# ATmega1284P.net
KiCad netlist of a schematic drawn in EAGLE
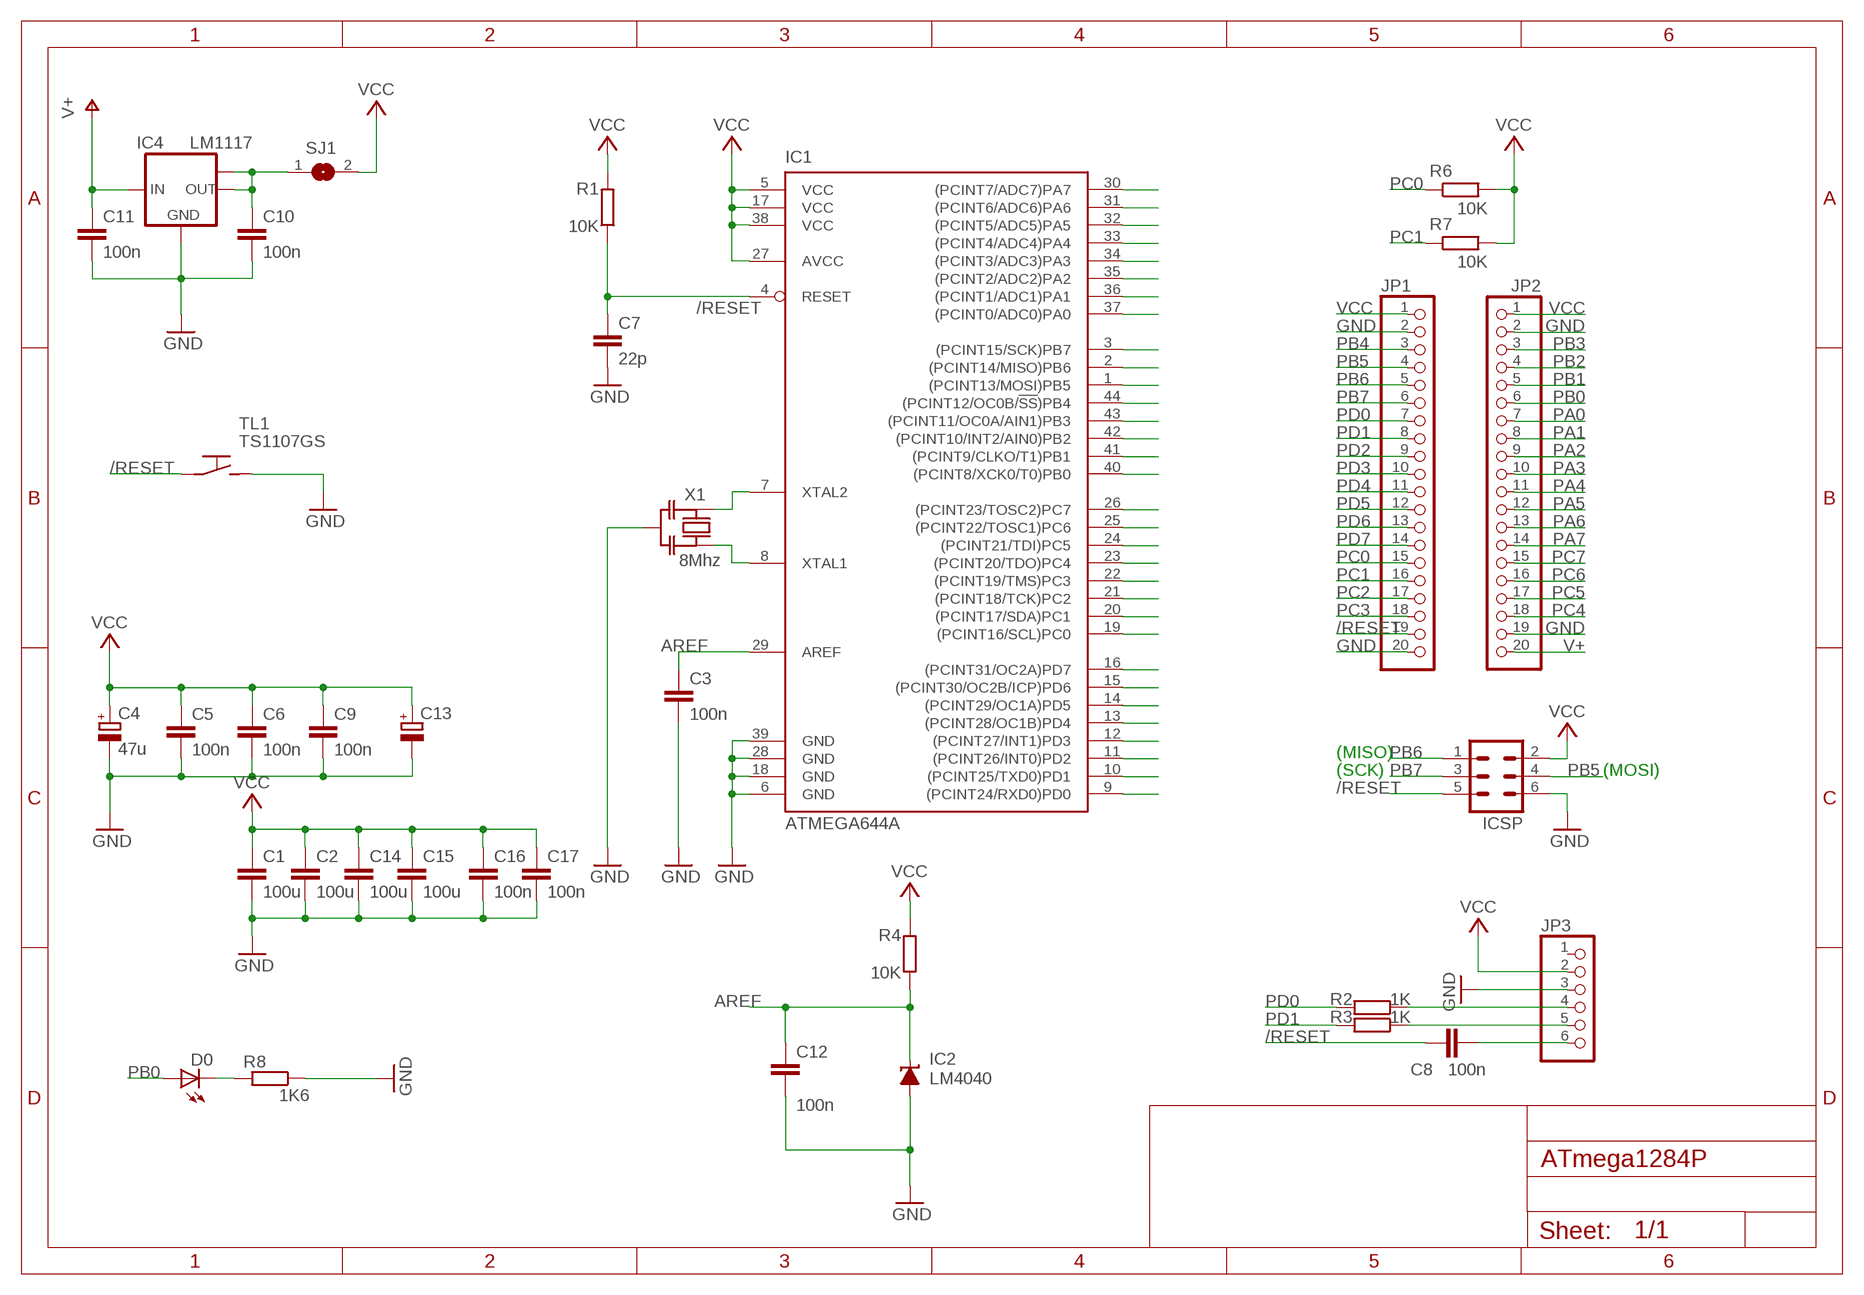
[diagram p0: schematic, sheet 1]

(export (version "E")
  (design (tool "Eeschema 10.0.6"))
  (components
    (comp (ref "C1")
      (value "100u")
      (footprint "eagle-import:C1206")
      (libsource (lib "eagle-import") (part "C-EUC1206"))
    )
    (comp (ref "C2")
      (value "100u")
      (footprint "eagle-import:C1206")
      (libsource (lib "eagle-import") (part "C-EUC1206"))
    )
    (comp (ref "C3")
      (value "100n")
      (footprint "eagle-import:C0805")
      (libsource (lib "eagle-import") (part "C-EUC0805"))
    )
    (comp (ref "C4")
      (value "47u")
      (footprint "eagle-import:SMC_A")
      (libsource (lib "eagle-import") (part "CPOL-EUSMCA"))
    )
    (comp (ref "C5")
      (value "100n")
      (footprint "eagle-import:C0805")
      (libsource (lib "eagle-import") (part "C-EUC0805"))
    )
    (comp (ref "C6")
      (value "100n")
      (footprint "eagle-import:C0805")
      (libsource (lib "eagle-import") (part "C-EUC0805"))
    )
    (comp (ref "C7")
      (value "22p")
      (footprint "eagle-import:C0805")
      (libsource (lib "eagle-import") (part "C-EUC0805"))
    )
    (comp (ref "C8")
      (value "100n")
      (footprint "eagle-import:C0805")
      (libsource (lib "eagle-import") (part "C-EUC0805"))
    )
    (comp (ref "C9")
      (value "100n")
      (footprint "eagle-import:C0805")
      (libsource (lib "eagle-import") (part "C-EUC0805"))
    )
    (comp (ref "C10")
      (value "100n")
      (footprint "eagle-import:C0805")
      (libsource (lib "eagle-import") (part "C-EUC0805"))
    )
    (comp (ref "C11")
      (value "100n")
      (footprint "eagle-import:C0805")
      (libsource (lib "eagle-import") (part "C-EUC0805"))
    )
    (comp (ref "C12")
      (value "100n")
      (footprint "eagle-import:C0805")
      (libsource (lib "eagle-import") (part "C-EUC0805"))
    )
    (comp (ref "C13")
      (value "CPOL-EUSMCC")
      (footprint "eagle-import:SMC_C")
      (libsource (lib "eagle-import") (part "CPOL-EUSMCC"))
    )
    (comp (ref "C14")
      (value "100u")
      (footprint "eagle-import:C1206")
      (libsource (lib "eagle-import") (part "C-EUC1206"))
    )
    (comp (ref "C15")
      (value "100u")
      (footprint "eagle-import:C1206")
      (libsource (lib "eagle-import") (part "C-EUC1206"))
    )
    (comp (ref "C16")
      (value "100n")
      (footprint "eagle-import:C0805")
      (libsource (lib "eagle-import") (part "C-EUC0805"))
    )
    (comp (ref "C17")
      (value "100n")
      (footprint "eagle-import:C0805")
      (libsource (lib "eagle-import") (part "C-EUC0805"))
    )
    (comp (ref "D0")
      (value "LEDCHIPLED_0805")
      (footprint "eagle-import:CHIPLED_0805")
      (libsource (lib "eagle-import") (part "LEDCHIPLED_0805"))
    )
    (comp (ref "IC1")
      (value "ATMEGA644A")
      (footprint "eagle-import:TQFP44")
      (fields (field (name "MPN") "ATMEGA644PV-10AU"))
      (libsource (lib "eagle-import") (part "ATMEGA644A"))
    )
    (comp (ref "IC2")
      (value "LM4040")
      (footprint "eagle-import:DBZ_R-PDSO-G3")
      (fields (field (name "MPN") "LM4041A12IDBZR"))
      (libsource (lib "eagle-import") (part "LM4041DBZA12"))
    )
    (comp (ref "IC4")
      (value "LM1117")
      (footprint "eagle-import:SOT223")
      (libsource (lib "eagle-import") (part "LM1117IMPX-3.3"))
    )
    (comp (ref "ICSP")
      (value "ML6")
      (footprint "eagle-import:ML6")
      (libsource (lib "eagle-import") (part "ML6"))
    )
    (comp (ref "JP1")
      (value "PINHD-1X20")
      (footprint "eagle-import:1X20")
      (libsource (lib "eagle-import") (part "PINHD-1X20"))
    )
    (comp (ref "JP2")
      (value "PINHD-1X20")
      (footprint "eagle-import:1X20")
      (libsource (lib "eagle-import") (part "PINHD-1X20"))
    )
    (comp (ref "JP3")
      (value "PINHD-1X6")
      (footprint "eagle-import:1X06")
      (libsource (lib "eagle-import") (part "PINHD-1X6"))
    )
    (comp (ref "R1")
      (value "10K")
      (footprint "eagle-import:M0805")
      (libsource (lib "eagle-import") (part "R-EU_M0805"))
    )
    (comp (ref "R2")
      (value "1K")
      (footprint "eagle-import:M0805")
      (libsource (lib "eagle-import") (part "R-EU_M0805"))
    )
    (comp (ref "R3")
      (value "1K")
      (footprint "eagle-import:M0805")
      (libsource (lib "eagle-import") (part "R-EU_M0805"))
    )
    (comp (ref "R4")
      (value "10K")
      (footprint "eagle-import:M0805")
      (libsource (lib "eagle-import") (part "R-EU_M0805"))
    )
    (comp (ref "R6")
      (value "10K")
      (footprint "eagle-import:M0805")
      (libsource (lib "eagle-import") (part "R-EU_M0805"))
    )
    (comp (ref "R7")
      (value "10K")
      (footprint "eagle-import:M0805")
      (libsource (lib "eagle-import") (part "R-EU_M0805"))
    )
    (comp (ref "R8")
      (value "1K6")
      (footprint "eagle-import:M0805")
      (libsource (lib "eagle-import") (part "R-EU_M0805"))
    )
    (comp (ref "SJ1") (value "SJ") (footprint "eagle-import:SJ") (libsource (lib "eagle-import") (part "SJ")))
    (comp (ref "TL1")
      (value "TS1107GS")
      (footprint "eagle-import:TS1107GS")
      (libsource (lib "eagle-import") (part "TS1107GS"))
    )
    (comp (ref "X1")
      (value "8Mhz")
      (footprint "eagle-import:CERALOCK_CSTCE_G")
      (libsource (lib "eagle-import") (part "CERMOSC-?CERALOCK-CSTCE_G"))
    )
  )
  (nets
    (net (code "1") (name "/AREF") (class "Default")
      (node (ref "C12") (pin "1") (pinfunction "1_1") (pintype "passive"))
      (node (ref "C3") (pin "2") (pinfunction "2_2") (pintype "passive"))
      (node (ref "IC1") (pin "29") (pinfunction "AREF_29") (pintype "passive"))
      (node (ref "IC2") (pin "1") (pinfunction "C_1") (pintype "passive"))
      (node (ref "R4") (pin "1") (pinfunction "1_1") (pintype "passive"))
    )
    (net (code "2") (name "/PA0") (class "Default")
      (node (ref "IC1") (pin "37") (pinfunction "(PCINT0/ADC0)PA0_37") (pintype "bidirectional"))
      (node (ref "JP2") (pin "7") (pinfunction "7_7") (pintype "passive"))
    )
    (net (code "3") (name "/PA1") (class "Default")
      (node (ref "IC1") (pin "36") (pinfunction "(PCINT1/ADC1)PA1_36") (pintype "bidirectional"))
      (node (ref "JP2") (pin "8") (pinfunction "8_8") (pintype "passive"))
    )
    (net (code "4") (name "/PA2") (class "Default")
      (node (ref "IC1") (pin "35") (pinfunction "(PCINT2/ADC2)PA2_35") (pintype "bidirectional"))
      (node (ref "JP2") (pin "9") (pinfunction "9_9") (pintype "passive"))
    )
    (net (code "5") (name "/PA3") (class "Default")
      (node (ref "IC1") (pin "34") (pinfunction "(PCINT3/ADC3)PA3_34") (pintype "bidirectional"))
      (node (ref "JP2") (pin "10") (pinfunction "10_10") (pintype "passive"))
    )
    (net (code "6") (name "/PA4") (class "Default")
      (node (ref "IC1") (pin "33") (pinfunction "(PCINT4/ADC4)PA4_33") (pintype "bidirectional"))
      (node (ref "JP2") (pin "11") (pinfunction "11_11") (pintype "passive"))
    )
    (net (code "7") (name "/PA5") (class "Default")
      (node (ref "IC1") (pin "32") (pinfunction "(PCINT5/ADC5)PA5_32") (pintype "bidirectional"))
      (node (ref "JP2") (pin "12") (pinfunction "12_12") (pintype "passive"))
    )
    (net (code "8") (name "/PA6") (class "Default")
      (node (ref "IC1") (pin "31") (pinfunction "(PCINT6/ADC6)PA6_31") (pintype "bidirectional"))
      (node (ref "JP2") (pin "13") (pinfunction "13_13") (pintype "passive"))
    )
    (net (code "9") (name "/PA7") (class "Default")
      (node (ref "IC1") (pin "30") (pinfunction "(PCINT7/ADC7)PA7_30") (pintype "bidirectional"))
      (node (ref "JP2") (pin "14") (pinfunction "14_14") (pintype "passive"))
    )
    (net (code "10") (name "/PB0") (class "Default")
      (node (ref "D0") (pin "A") (pinfunction "A_A") (pintype "passive"))
      (node (ref "IC1") (pin "40") (pinfunction "(PCINT8/XCK0/T0)PB0_40") (pintype "bidirectional"))
      (node (ref "JP2") (pin "6") (pinfunction "6_6") (pintype "passive"))
    )
    (net (code "11") (name "/PB1") (class "Default")
      (node (ref "IC1") (pin "41") (pinfunction "(PCINT9/CLKO/T1)PB1_41") (pintype "bidirectional"))
      (node (ref "JP2") (pin "5") (pinfunction "5_5") (pintype "passive"))
    )
    (net (code "12") (name "/PB2") (class "Default")
      (node (ref "IC1") (pin "42") (pinfunction "(PCINT10/INT2/AIN0)PB2_42") (pintype "bidirectional"))
      (node (ref "JP2") (pin "4") (pinfunction "4_4") (pintype "passive"))
    )
    (net (code "13") (name "/PB3") (class "Default")
      (node (ref "IC1") (pin "43") (pinfunction "(PCINT11/OC0A/AIN1)PB3_43") (pintype "bidirectional"))
      (node (ref "JP2") (pin "3") (pinfunction "3_3") (pintype "passive"))
    )
    (net (code "14") (name "/PB4") (class "Default")
      (node (ref "IC1") (pin "44") (pinfunction "(PCINT12/OC0B/~{SS})PB4_44") (pintype "bidirectional"))
      (node (ref "JP1") (pin "3") (pinfunction "3_3") (pintype "passive"))
    )
    (net (code "15") (name "/PB5") (class "Default")
      (node (ref "IC1") (pin "1") (pinfunction "(PCINT13/MOSI)PB5_1") (pintype "bidirectional"))
      (node (ref "ICSP") (pin "4") (pinfunction "4_4") (pintype "passive"))
      (node (ref "JP1") (pin "4") (pinfunction "4_4") (pintype "passive"))
    )
    (net (code "16") (name "/PB6") (class "Default")
      (node (ref "IC1") (pin "2") (pinfunction "(PCINT14/MISO)PB6_2") (pintype "bidirectional"))
      (node (ref "ICSP") (pin "1") (pinfunction "1_1") (pintype "passive"))
      (node (ref "JP1") (pin "5") (pinfunction "5_5") (pintype "passive"))
    )
    (net (code "17") (name "/PB7") (class "Default")
      (node (ref "IC1") (pin "3") (pinfunction "(PCINT15/SCK)PB7_3") (pintype "bidirectional"))
      (node (ref "ICSP") (pin "3") (pinfunction "3_3") (pintype "passive"))
      (node (ref "JP1") (pin "6") (pinfunction "6_6") (pintype "passive"))
    )
    (net (code "18") (name "/PC0") (class "Default")
      (node (ref "IC1") (pin "19") (pinfunction "(PCINT16/SCL)PC0_19") (pintype "output"))
      (node (ref "JP1") (pin "15") (pinfunction "15_15") (pintype "passive"))
      (node (ref "R6") (pin "1") (pinfunction "1_1") (pintype "passive"))
    )
    (net (code "19") (name "/PC1") (class "Default")
      (node (ref "IC1") (pin "20") (pinfunction "(PCINT17/SDA)PC1_20") (pintype "output"))
      (node (ref "JP1") (pin "16") (pinfunction "16_16") (pintype "passive"))
      (node (ref "R7") (pin "1") (pinfunction "1_1") (pintype "passive"))
    )
    (net (code "20") (name "/PC2") (class "Default")
      (node (ref "IC1") (pin "21") (pinfunction "(PCINT18/TCK)PC2_21") (pintype "output"))
      (node (ref "JP1") (pin "17") (pinfunction "17_17") (pintype "passive"))
    )
    (net (code "21") (name "/PC3") (class "Default")
      (node (ref "IC1") (pin "22") (pinfunction "(PCINT19/TMS)PC3_22") (pintype "output"))
      (node (ref "JP1") (pin "18") (pinfunction "18_18") (pintype "passive"))
    )
    (net (code "22") (name "/PC4") (class "Default")
      (node (ref "IC1") (pin "23") (pinfunction "(PCINT20/TDO)PC4_23") (pintype "output"))
      (node (ref "JP2") (pin "18") (pinfunction "18_18") (pintype "passive"))
    )
    (net (code "23") (name "/PC5") (class "Default")
      (node (ref "IC1") (pin "24") (pinfunction "(PCINT21/TDI)PC5_24") (pintype "output"))
      (node (ref "JP2") (pin "17") (pinfunction "17_17") (pintype "passive"))
    )
    (net (code "24") (name "/PC6") (class "Default")
      (node (ref "IC1") (pin "25") (pinfunction "(PCINT22/TOSC1)PC6_25") (pintype "output"))
      (node (ref "JP2") (pin "16") (pinfunction "16_16") (pintype "passive"))
    )
    (net (code "25") (name "/PC7") (class "Default")
      (node (ref "IC1") (pin "26") (pinfunction "(PCINT23/TOSC2)PC7_26") (pintype "output"))
      (node (ref "JP2") (pin "15") (pinfunction "15_15") (pintype "passive"))
    )
    (net (code "26") (name "/PD0") (class "Default")
      (node (ref "IC1") (pin "9") (pinfunction "(PCINT24/RXD0)PD0_9") (pintype "bidirectional"))
      (node (ref "JP1") (pin "7") (pinfunction "7_7") (pintype "passive"))
      (node (ref "R2") (pin "2") (pinfunction "2_2") (pintype "passive"))
    )
    (net (code "27") (name "/PD1") (class "Default")
      (node (ref "IC1") (pin "10") (pinfunction "(PCINT25/TXD0)PD1_10") (pintype "bidirectional"))
      (node (ref "JP1") (pin "8") (pinfunction "8_8") (pintype "passive"))
      (node (ref "R3") (pin "2") (pinfunction "2_2") (pintype "passive"))
    )
    (net (code "28") (name "/PD2") (class "Default")
      (node (ref "IC1") (pin "11") (pinfunction "(PCINT26/INT0)PD2_11") (pintype "bidirectional"))
      (node (ref "JP1") (pin "9") (pinfunction "9_9") (pintype "passive"))
    )
    (net (code "29") (name "/PD3") (class "Default")
      (node (ref "IC1") (pin "12") (pinfunction "(PCINT27/INT1)PD3_12") (pintype "bidirectional"))
      (node (ref "JP1") (pin "10") (pinfunction "10_10") (pintype "passive"))
    )
    (net (code "30") (name "/PD4") (class "Default")
      (node (ref "IC1") (pin "13") (pinfunction "(PCINT28/OC1B)PD4_13") (pintype "bidirectional"))
      (node (ref "JP1") (pin "11") (pinfunction "11_11") (pintype "passive"))
    )
    (net (code "31") (name "/PD5") (class "Default")
      (node (ref "IC1") (pin "14") (pinfunction "(PCINT29/OC1A)PD5_14") (pintype "bidirectional"))
      (node (ref "JP1") (pin "12") (pinfunction "12_12") (pintype "passive"))
    )
    (net (code "32") (name "/PD6") (class "Default")
      (node (ref "IC1") (pin "15") (pinfunction "(PCINT30/OC2B/ICP)PD6_15") (pintype "bidirectional"))
      (node (ref "JP1") (pin "13") (pinfunction "13_13") (pintype "passive"))
    )
    (net (code "33") (name "/PD7") (class "Default")
      (node (ref "IC1") (pin "16") (pinfunction "(PCINT31/OC2A)PD7_16") (pintype "bidirectional"))
      (node (ref "JP1") (pin "14") (pinfunction "14_14") (pintype "passive"))
    )
    (net (code "34") (name "/{slash}RESET") (class "Default")
      (node (ref "C7") (pin "2") (pinfunction "2_2") (pintype "passive"))
      (node (ref "C8") (pin "2") (pinfunction "2_2") (pintype "passive"))
      (node (ref "IC1") (pin "4") (pinfunction "RESET_4") (pintype "input"))
      (node (ref "ICSP") (pin "5") (pinfunction "5_5") (pintype "passive"))
      (node (ref "JP1") (pin "19") (pinfunction "19_19") (pintype "passive"))
      (node (ref "R1") (pin "1") (pinfunction "1_1") (pintype "passive"))
      (node (ref "TL1") (pin "P$1") (pinfunction "P_P$1") (pintype "passive"))
    )
    (net (code "35") (name "GND") (class "Default")
      (node (ref "C1") (pin "2") (pinfunction "2_2") (pintype "passive"))
      (node (ref "C10") (pin "2") (pinfunction "2_2") (pintype "passive"))
      (node (ref "C11") (pin "2") (pinfunction "2_2") (pintype "passive"))
      (node (ref "C12") (pin "2") (pinfunction "2_2") (pintype "passive"))
      (node (ref "C13") (pin "-") (pinfunction "-_-") (pintype "passive"))
      (node (ref "C14") (pin "2") (pinfunction "2_2") (pintype "passive"))
      (node (ref "C15") (pin "2") (pinfunction "2_2") (pintype "passive"))
      (node (ref "C16") (pin "1") (pinfunction "1_1") (pintype "passive"))
      (node (ref "C17") (pin "1") (pinfunction "1_1") (pintype "passive"))
      (node (ref "C2") (pin "2") (pinfunction "2_2") (pintype "passive"))
      (node (ref "C3") (pin "1") (pinfunction "1_1") (pintype "passive"))
      (node (ref "C4") (pin "-") (pinfunction "-_-") (pintype "passive"))
      (node (ref "C5") (pin "1") (pinfunction "1_1") (pintype "passive"))
      (node (ref "C6") (pin "1") (pinfunction "1_1") (pintype "passive"))
      (node (ref "C7") (pin "1") (pinfunction "1_1") (pintype "passive"))
      (node (ref "C9") (pin "1") (pinfunction "1_1") (pintype "passive"))
      (node (ref "IC1") (pin "18") (pinfunction "GND_18") (pintype "power_in"))
      (node (ref "IC1") (pin "28") (pinfunction "GND_28") (pintype "power_in"))
      (node (ref "IC1") (pin "39") (pinfunction "GND_39") (pintype "power_in"))
      (node (ref "IC1") (pin "6") (pinfunction "GND_6") (pintype "power_in"))
      (node (ref "IC2") (pin "2") (pinfunction "A_2") (pintype "passive"))
      (node (ref "IC4") (pin "1") (pinfunction "GND_1") (pintype "input"))
      (node (ref "ICSP") (pin "6") (pinfunction "6_6") (pintype "passive"))
      (node (ref "JP1") (pin "2") (pinfunction "2_2") (pintype "passive"))
      (node (ref "JP1") (pin "20") (pinfunction "20_20") (pintype "passive"))
      (node (ref "JP2") (pin "19") (pinfunction "19_19") (pintype "passive"))
      (node (ref "JP2") (pin "2") (pinfunction "2_2") (pintype "passive"))
      (node (ref "JP3") (pin "3") (pinfunction "3_3") (pintype "passive"))
      (node (ref "R8") (pin "1") (pinfunction "1_1") (pintype "passive"))
      (node (ref "TL1") (pin "P$2") (pinfunction "S_P$2") (pintype "passive"))
      (node (ref "X1") (pin "P$2") (pinfunction "GND_P$2") (pintype "passive"))
    )
    (net (code "36") (name "Net-(C8-Pad1)") (class "Default")
      (node (ref "C8") (pin "1") (pinfunction "1_1") (pintype "passive"))
      (node (ref "JP3") (pin "6") (pinfunction "6_6") (pintype "passive"))
    )
    (net (code "37") (name "Net-(D0-PadC)") (class "Default")
      (node (ref "D0") (pin "C") (pinfunction "C_C") (pintype "passive"))
      (node (ref "R8") (pin "2") (pinfunction "2_2") (pintype "passive"))
    )
    (net (code "38") (name "Net-(IC1-XTAL1)") (class "Default")
      (node (ref "IC1") (pin "8") (pinfunction "XTAL1_8") (pintype "bidirectional"))
      (node (ref "X1") (pin "P$1") (pinfunction "1_P$1") (pintype "passive"))
    )
    (net (code "39") (name "Net-(IC1-XTAL2)") (class "Default")
      (node (ref "IC1") (pin "7") (pinfunction "XTAL2_7") (pintype "bidirectional"))
      (node (ref "X1") (pin "P$3") (pinfunction "2_P$3") (pintype "passive"))
    )
    (net (code "40") (name "Net-(IC4-OUT)") (class "Default")
      (node (ref "C10") (pin "1") (pinfunction "1_1") (pintype "passive"))
      (node (ref "IC4") (pin "2") (pinfunction "OUT_2") (pintype "passive"))
      (node (ref "IC4") (pin "TAB") (pinfunction "OUT1_TAB") (pintype "passive"))
      (node (ref "SJ1") (pin "1") (pinfunction "1_1") (pintype "passive"))
    )
    (net (code "41") (name "Net-(JP3-Pad4)") (class "Default")
      (node (ref "JP3") (pin "4") (pinfunction "4_4") (pintype "passive"))
      (node (ref "R2") (pin "1") (pinfunction "1_1") (pintype "passive"))
    )
    (net (code "42") (name "Net-(JP3-Pad5)") (class "Default")
      (node (ref "JP3") (pin "5") (pinfunction "5_5") (pintype "passive"))
      (node (ref "R3") (pin "1") (pinfunction "1_1") (pintype "passive"))
    )
    (net (code "43") (name "V+") (class "Default")
      (node (ref "C11") (pin "1") (pinfunction "1_1") (pintype "passive"))
      (node (ref "IC4") (pin "3") (pinfunction "IN_3") (pintype "input"))
      (node (ref "JP2") (pin "20") (pinfunction "20_20") (pintype "passive"))
    )
    (net (code "44") (name "VCC") (class "Default")
      (node (ref "C1") (pin "1") (pinfunction "1_1") (pintype "passive"))
      (node (ref "C13") (pin "+") (pinfunction "+_+") (pintype "passive"))
      (node (ref "C14") (pin "1") (pinfunction "1_1") (pintype "passive"))
      (node (ref "C15") (pin "1") (pinfunction "1_1") (pintype "passive"))
      (node (ref "C16") (pin "2") (pinfunction "2_2") (pintype "passive"))
      (node (ref "C17") (pin "2") (pinfunction "2_2") (pintype "passive"))
      (node (ref "C2") (pin "1") (pinfunction "1_1") (pintype "passive"))
      (node (ref "C4") (pin "+") (pinfunction "+_+") (pintype "passive"))
      (node (ref "C5") (pin "2") (pinfunction "2_2") (pintype "passive"))
      (node (ref "C6") (pin "2") (pinfunction "2_2") (pintype "passive"))
      (node (ref "C9") (pin "2") (pinfunction "2_2") (pintype "passive"))
      (node (ref "IC1") (pin "17") (pinfunction "VCC_17") (pintype "power_in"))
      (node (ref "IC1") (pin "27") (pinfunction "AVCC_27") (pintype "power_in"))
      (node (ref "IC1") (pin "38") (pinfunction "VCC_38") (pintype "power_in"))
      (node (ref "IC1") (pin "5") (pinfunction "VCC_5") (pintype "power_in"))
      (node (ref "ICSP") (pin "2") (pinfunction "2_2") (pintype "passive"))
      (node (ref "JP1") (pin "1") (pinfunction "1_1") (pintype "passive"))
      (node (ref "JP2") (pin "1") (pinfunction "1_1") (pintype "passive"))
      (node (ref "JP3") (pin "2") (pinfunction "2_2") (pintype "passive"))
      (node (ref "R1") (pin "2") (pinfunction "2_2") (pintype "passive"))
      (node (ref "R4") (pin "2") (pinfunction "2_2") (pintype "passive"))
      (node (ref "R6") (pin "2") (pinfunction "2_2") (pintype "passive"))
      (node (ref "R7") (pin "2") (pinfunction "2_2") (pintype "passive"))
      (node (ref "SJ1") (pin "2") (pinfunction "2_2") (pintype "passive"))
    )
    (net (code "45") (name "unconnected-(JP3-Pad1)") (class "Default")
      (node (ref "JP3") (pin "1") (pinfunction "1_1") (pintype "passive"))
    )
  )
)
